# Verna_Dorian_334CC.net
KiCad netlist of a schematic drawn in EAGLE
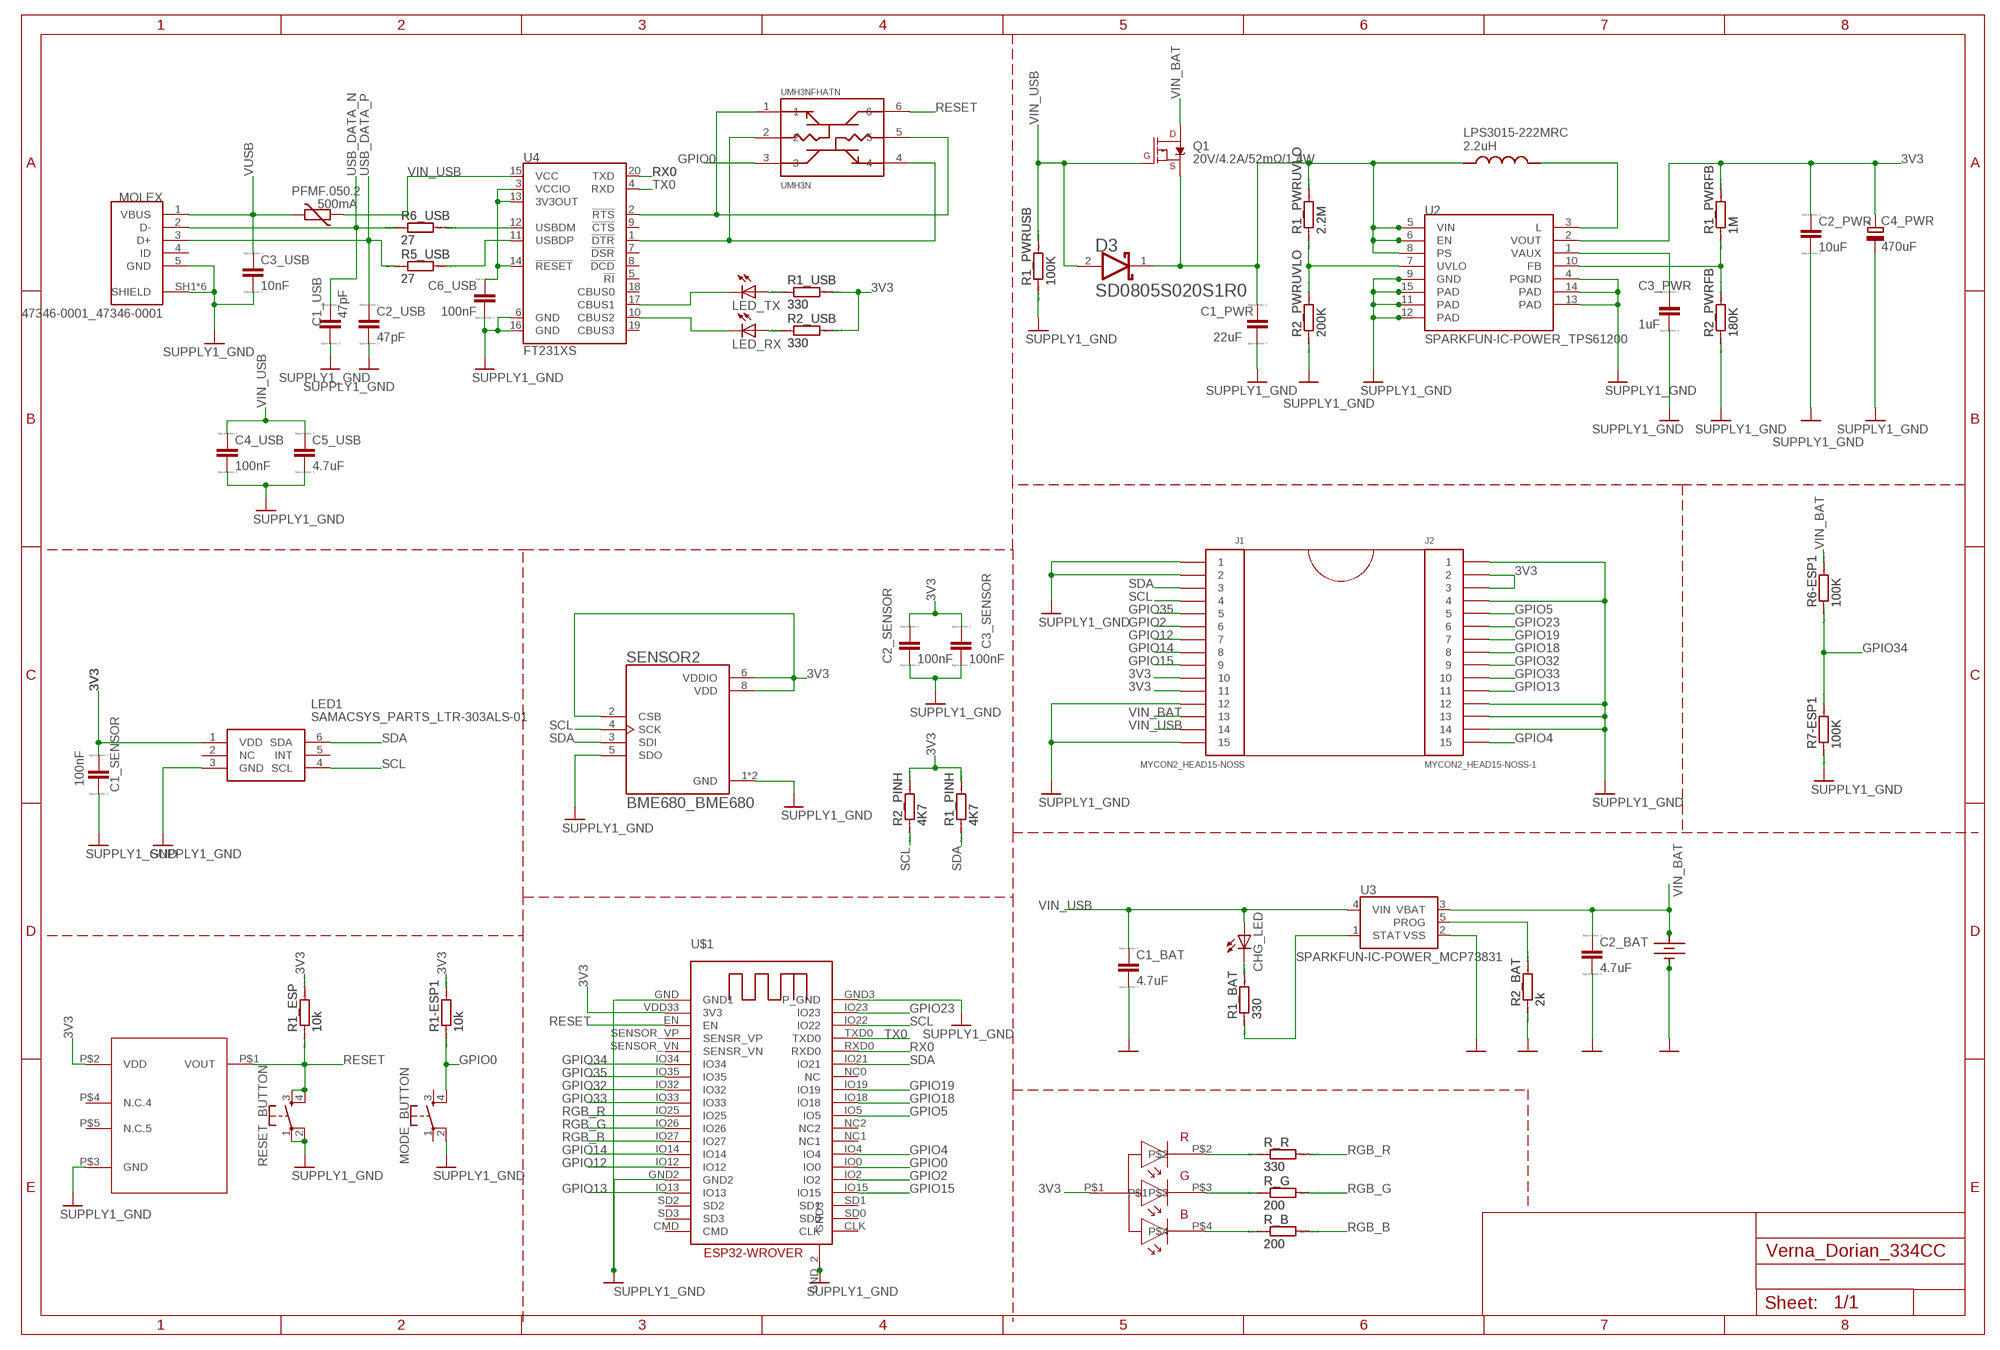
[diagram p0: schematic, sheet 1]

(export (version "E")
  (design (tool "Eeschema 10.0.6"))
  (components
    (comp (ref "18650BATTHOLDER")
      (value "12BHC186CLP-GR_12BHC186CLP-GR")
      (footprint "eagle-import:12BHC186CLP-GR_12BHC186CLP-GR")
      (libsource (lib "eagle-import") (part "12BHC186CLP-GR_12BHC186CLP-GR"))
    )
    (comp (ref "C1_BAT")
      (value "4.7uF")
      (footprint "eagle-import:EAGLE-LTSPICE_C0402")
      (libsource (lib "eagle-import") (part "EAGLE-LTSPICE_CC0402"))
    )
    (comp (ref "C1_PWR")
      (value "22uF")
      (footprint "eagle-import:EAGLE-LTSPICE_C0402")
      (libsource (lib "eagle-import") (part "EAGLE-LTSPICE_CC0402"))
    )
    (comp (ref "C1_SENSOR")
      (value "100nF")
      (footprint "eagle-import:EAGLE-LTSPICE_C0402")
      (libsource (lib "eagle-import") (part "EAGLE-LTSPICE_CC0402"))
    )
    (comp (ref "C1_USB")
      (value "47pF")
      (footprint "eagle-import:EAGLE-LTSPICE_C0402")
      (libsource (lib "eagle-import") (part "EAGLE-LTSPICE_CC0402"))
    )
    (comp (ref "C2_BAT")
      (value "4.7uF")
      (footprint "eagle-import:EAGLE-LTSPICE_C0402")
      (libsource (lib "eagle-import") (part "EAGLE-LTSPICE_CC0402"))
    )
    (comp (ref "C2_PWR")
      (value "10uF")
      (footprint "eagle-import:EAGLE-LTSPICE_C0402")
      (libsource (lib "eagle-import") (part "EAGLE-LTSPICE_CC0402"))
    )
    (comp (ref "C2_SENSOR")
      (value "100nF")
      (footprint "eagle-import:EAGLE-LTSPICE_C0402")
      (libsource (lib "eagle-import") (part "EAGLE-LTSPICE_CC0402"))
    )
    (comp (ref "C2_USB")
      (value "47pF")
      (footprint "eagle-import:EAGLE-LTSPICE_C0402")
      (libsource (lib "eagle-import") (part "EAGLE-LTSPICE_CC0402"))
    )
    (comp (ref "C3_PWR")
      (value "1uF")
      (footprint "eagle-import:EAGLE-LTSPICE_C0402")
      (libsource (lib "eagle-import") (part "EAGLE-LTSPICE_CC0402"))
    )
    (comp (ref "C3_SENSOR")
      (value "100nF")
      (footprint "eagle-import:EAGLE-LTSPICE_C0402")
      (libsource (lib "eagle-import") (part "EAGLE-LTSPICE_CC0402"))
    )
    (comp (ref "C3_USB")
      (value "10nF")
      (footprint "eagle-import:EAGLE-LTSPICE_C0402")
      (libsource (lib "eagle-import") (part "EAGLE-LTSPICE_CC0402"))
    )
    (comp (ref "C4_PWR")
      (value "470uF")
      (footprint "eagle-import:RCL_D_7343-31R")
      (libsource (lib "eagle-import") (part "RCL_CPOL-EUD/7343-31R"))
    )
    (comp (ref "C4_USB")
      (value "100nF")
      (footprint "eagle-import:EAGLE-LTSPICE_C0402")
      (libsource (lib "eagle-import") (part "EAGLE-LTSPICE_CC0402"))
    )
    (comp (ref "C5_USB")
      (value "4.7uF")
      (footprint "eagle-import:EAGLE-LTSPICE_C0402")
      (libsource (lib "eagle-import") (part "EAGLE-LTSPICE_CC0402"))
    )
    (comp (ref "C6_USB")
      (value "100nF")
      (footprint "eagle-import:EAGLE-LTSPICE_C0402")
      (libsource (lib "eagle-import") (part "EAGLE-LTSPICE_CC0402"))
    )
    (comp (ref "CHG_LED")
      (value "ADAFRUIT_LEDCHIP-LED0603")
      (footprint "eagle-import:ADAFRUIT_CHIP-LED0603")
      (libsource (lib "eagle-import") (part "ADAFRUIT_LEDCHIP-LED0603"))
    )
    (comp (ref "D3")
      (value "AVX---SD0805S020S1R0_AVX_SD0805S020S1R0AVX_SD0805S020S1R0_0_0")
      (footprint "eagle-import:AVX---SD0805S020S1R0_AVX_SD0805S020S1R0_0")
      (fields
        (field (name "DIGIKEY_PART_NUMBER") "478-7800-1-ND")
        (field (name "MF") "AVX")
        (field (name "MOUSER_PART_NUMBER") "581-SD0805S020S1R0")
      )
      (libsource (lib "eagle-import") (part "AVX---SD0805S020S1R0_AVX_SD0805S020S1R0AVX_SD0805S020S1R0_0_0"))
    )
    (comp (ref "J1")
      (value "MYCON2_HEAD15-NOSS")
      (footprint "eagle-import:MYCON2_HEAD15-NOSS")
      (libsource (lib "eagle-import") (part "MYCON2_HEAD15-NOSS"))
    )
    (comp (ref "J2")
      (value "MYCON2_HEAD15-NOSS-1")
      (footprint "eagle-import:MYCON2_HEAD15-NOSS-1")
      (libsource (lib "eagle-import") (part "MYCON2_HEAD15-NOSS-1"))
    )
    (comp (ref "LED1")
      (value "SAMACSYS_PARTS_LTR-303ALS-01")
      (footprint "eagle-import:SAMACSYS_PARTS_LTR303ALS01")
      (fields
        (field (name "ARROW_PART_NUMBER") "LTR-303ALS-01")
        (field (name "MOUSER_PART_NUMBER") "859-LTR-303ALS-01")
      )
      (libsource (lib "eagle-import") (part "SAMACSYS_PARTS_LTR-303ALS-01"))
    )
    (comp (ref "LED_RX")
      (value "ADAFRUIT_LEDCHIP-LED0603")
      (footprint "eagle-import:ADAFRUIT_CHIP-LED0603")
      (libsource (lib "eagle-import") (part "ADAFRUIT_LEDCHIP-LED0603"))
    )
    (comp (ref "LED_TX")
      (value "ADAFRUIT_LEDCHIP-LED0603")
      (footprint "eagle-import:ADAFRUIT_CHIP-LED0603")
      (libsource (lib "eagle-import") (part "ADAFRUIT_LEDCHIP-LED0603"))
    )
    (comp (ref "MODE_BUTTON")
      (value "SPARKFUN-SWITCHES_MOMENTARY-SWITCH-SPST-2-SMD-4.6X2.8MM")
      (footprint "eagle-import:SPARKFUN-SWITCHES_TACTILE_SWITCH_SMD_4.6X2.8MM")
      (libsource (lib "eagle-import") (part "SPARKFUN-SWITCHES_MOMENTARY-SWITCH-SPST-2-SMD-4.6X2.8MM"))
    )
    (comp (ref "MOLEX")
      (value "47346-0001_47346-0001")
      (footprint "eagle-import:47346-0001_MOLEX_47346-0001")
      (fields (field (name "MF") "Molex") (field (name "MP") "47346-0001"))
      (libsource (lib "eagle-import") (part "47346-0001_47346-0001"))
    )
    (comp (ref "PFMF.050.2")
      (value "500mA")
      (footprint "eagle-import:VARISTOR_CT_CN1812")
      (libsource (lib "eagle-import") (part "VARISTOR_VARISTORCN1812"))
    )
    (comp (ref "Q1")
      (value "20V/4.2A/52mΩ/1.4W")
      (footprint "eagle-import:SPARKFUN-DISCRETESEMI_SOT23-3")
      (libsource (lib "eagle-import") (part "SPARKFUN-DISCRETESEMI_MOSFET_PCH-DMG2305UX-7"))
    )
    (comp (ref "R1-ESP1")
      (value "10k")
      (footprint "eagle-import:EAGLE-LTSPICE_R0402")
      (libsource (lib "eagle-import") (part "EAGLE-LTSPICE_RR0402"))
    )
    (comp (ref "R1_BAT")
      (value "330")
      (footprint "eagle-import:EAGLE-LTSPICE_R0402")
      (libsource (lib "eagle-import") (part "EAGLE-LTSPICE_RR0402"))
    )
    (comp (ref "R1_ESP")
      (value "10k")
      (footprint "eagle-import:EAGLE-LTSPICE_R0402")
      (libsource (lib "eagle-import") (part "EAGLE-LTSPICE_RR0402"))
    )
    (comp (ref "R1_PINH")
      (value "4K7")
      (footprint "eagle-import:EAGLE-LTSPICE_R0402")
      (libsource (lib "eagle-import") (part "EAGLE-LTSPICE_RR0402"))
    )
    (comp (ref "R1_PWRFB")
      (value "1M")
      (footprint "eagle-import:EAGLE-LTSPICE_R0402")
      (libsource (lib "eagle-import") (part "EAGLE-LTSPICE_RR0402"))
    )
    (comp (ref "R1_PWRUSB")
      (value "100K")
      (footprint "eagle-import:EAGLE-LTSPICE_R0402")
      (libsource (lib "eagle-import") (part "EAGLE-LTSPICE_RR0402"))
    )
    (comp (ref "R1_PWRUVLO")
      (value "2.2M")
      (footprint "eagle-import:EAGLE-LTSPICE_R0402")
      (libsource (lib "eagle-import") (part "EAGLE-LTSPICE_RR0402"))
    )
    (comp (ref "R1_USB")
      (value "330")
      (footprint "eagle-import:EAGLE-LTSPICE_R0402")
      (libsource (lib "eagle-import") (part "EAGLE-LTSPICE_RR0402"))
    )
    (comp (ref "R2_BAT")
      (value "2k")
      (footprint "eagle-import:EAGLE-LTSPICE_R0402")
      (libsource (lib "eagle-import") (part "EAGLE-LTSPICE_RR0402"))
    )
    (comp (ref "R2_PINH")
      (value "4K7")
      (footprint "eagle-import:EAGLE-LTSPICE_R0402")
      (libsource (lib "eagle-import") (part "EAGLE-LTSPICE_RR0402"))
    )
    (comp (ref "R2_PWRFB")
      (value "180K")
      (footprint "eagle-import:EAGLE-LTSPICE_R0402")
      (libsource (lib "eagle-import") (part "EAGLE-LTSPICE_RR0402"))
    )
    (comp (ref "R2_PWRUVLO")
      (value "200K")
      (footprint "eagle-import:EAGLE-LTSPICE_R0402")
      (libsource (lib "eagle-import") (part "EAGLE-LTSPICE_RR0402"))
    )
    (comp (ref "R2_USB")
      (value "330")
      (footprint "eagle-import:EAGLE-LTSPICE_R0402")
      (libsource (lib "eagle-import") (part "EAGLE-LTSPICE_RR0402"))
    )
    (comp (ref "R5_USB")
      (value "27")
      (footprint "eagle-import:EAGLE-LTSPICE_R0402")
      (libsource (lib "eagle-import") (part "EAGLE-LTSPICE_RR0402"))
    )
    (comp (ref "R6-ESP1")
      (value "100K")
      (footprint "eagle-import:EAGLE-LTSPICE_R0402")
      (libsource (lib "eagle-import") (part "EAGLE-LTSPICE_RR0402"))
    )
    (comp (ref "R6_USB")
      (value "27")
      (footprint "eagle-import:EAGLE-LTSPICE_R0402")
      (libsource (lib "eagle-import") (part "EAGLE-LTSPICE_RR0402"))
    )
    (comp (ref "R7-ESP1")
      (value "100K")
      (footprint "eagle-import:EAGLE-LTSPICE_R0402")
      (libsource (lib "eagle-import") (part "EAGLE-LTSPICE_RR0402"))
    )
    (comp (ref "RESET_BUTTON")
      (value "SPARKFUN-SWITCHES_MOMENTARY-SWITCH-SPST-2-SMD-4.6X2.8MM")
      (footprint "eagle-import:SPARKFUN-SWITCHES_TACTILE_SWITCH_SMD_4.6X2.8MM")
      (libsource (lib "eagle-import") (part "SPARKFUN-SWITCHES_MOMENTARY-SWITCH-SPST-2-SMD-4.6X2.8MM"))
    )
    (comp (ref "R_B")
      (value "200")
      (footprint "eagle-import:EAGLE-LTSPICE_R0402")
      (libsource (lib "eagle-import") (part "EAGLE-LTSPICE_RR0402"))
    )
    (comp (ref "R_G")
      (value "200")
      (footprint "eagle-import:EAGLE-LTSPICE_R0402")
      (libsource (lib "eagle-import") (part "EAGLE-LTSPICE_RR0402"))
    )
    (comp (ref "R_R")
      (value "330")
      (footprint "eagle-import:EAGLE-LTSPICE_R0402")
      (libsource (lib "eagle-import") (part "EAGLE-LTSPICE_RR0402"))
    )
    (comp (ref "SENSOR2")
      (value "BME680_BME680")
      (footprint "eagle-import:BME680_PSON80P300X300X100-8N")
      (fields (field (name "MF") "Bosch Sensortec") (field (name "MP") "BME680"))
      (libsource (lib "eagle-import") (part "BME680_BME680"))
    )
    (comp (ref "U$1")
      (value "ESP32-WROVER_ESP32-WROVER")
      (footprint "eagle-import:ESP32-WROVER_ESP32-WROVER")
      (libsource (lib "eagle-import") (part "ESP32-WROVER_ESP32-WROVER"))
    )
    (comp (ref "U$2")
      (value "150202M153130_150202M153130-RGB")
      (footprint "eagle-import:150202M153130_150202M153130")
      (libsource (lib "eagle-import") (part "150202M153130_150202M153130-RGB"))
    )
    (comp (ref "U$3")
      (value "BD48E27G-TR_BD48E27G-TR")
      (footprint "eagle-import:BD48E27G-TR_SSOP5")
      (libsource (lib "eagle-import") (part "BD48E27G-TR_BD48E27G-TR"))
    )
    (comp (ref "U$6")
      (value "LPS3015_LPS3015")
      (footprint "eagle-import:LPS3015_LPS3015-222MRC")
      (libsource (lib "eagle-import") (part "LPS3015_LPS3015"))
    )
    (comp (ref "U2")
      (value "SPARKFUN-IC-POWER_TPS61200")
      (footprint "eagle-import:SPARKFUN-IC-POWER_QFN-10_PAD")
      (libsource (lib "eagle-import") (part "SPARKFUN-IC-POWER_TPS61200"))
    )
    (comp (ref "U3")
      (value "SPARKFUN-IC-POWER_MCP73831")
      (footprint "eagle-import:SPARKFUN-IC-POWER_SOT23-5")
      (libsource (lib "eagle-import") (part "SPARKFUN-IC-POWER_MCP73831"))
    )
    (comp (ref "U4")
      (value "FT231XS")
      (footprint "eagle-import:SPARKFUN-IC-COMMS_SSOP20_L")
      (libsource (lib "eagle-import") (part "SPARKFUN-IC-COMMS_FT231XS"))
    )
    (comp (ref "UMH3NFHATN")
      (value "UMH3N_UMH3N")
      (footprint "eagle-import:UMH3N_SOP65P210X100-6N")
      (fields (field (name "MF") "Rohm") (field (name "MP") "UMH3N"))
      (libsource (lib "eagle-import") (part "UMH3N_UMH3N"))
    )
  )
  (nets
    (net (code "1") (name "/3V3") (class "Default")
      (node (ref "C1_SENSOR") (pin "1") (pinfunction "1_1") (pintype "passive"))
      (node (ref "C2_PWR") (pin "1") (pinfunction "1_1") (pintype "passive"))
      (node (ref "C2_SENSOR") (pin "1") (pinfunction "1_1") (pintype "passive"))
      (node (ref "C3_SENSOR") (pin "1") (pinfunction "1_1") (pintype "passive"))
      (node (ref "C4_PWR") (pin "+") (pinfunction "+_+") (pintype "passive"))
      (node (ref "J1") (pin "10") (pinfunction "10_10") (pintype "passive"))
      (node (ref "J1") (pin "11") (pinfunction "11_11") (pintype "passive"))
      (node (ref "J2") (pin "2") (pinfunction "2_2") (pintype "passive"))
      (node (ref "J2") (pin "3") (pinfunction "3_3") (pintype "passive"))
      (node (ref "LED1") (pin "1") (pinfunction "VDD_1") (pintype "bidirectional"))
      (node (ref "R1-ESP1") (pin "2") (pinfunction "2_2") (pintype "passive"))
      (node (ref "R1_ESP") (pin "2") (pinfunction "2_2") (pintype "passive"))
      (node (ref "R1_PINH") (pin "2") (pinfunction "2_2") (pintype "passive"))
      (node (ref "R1_PWRFB") (pin "2") (pinfunction "2_2") (pintype "passive"))
      (node (ref "R1_USB") (pin "2") (pinfunction "2_2") (pintype "passive"))
      (node (ref "R2_PINH") (pin "2") (pinfunction "2_2") (pintype "passive"))
      (node (ref "R2_USB") (pin "2") (pinfunction "2_2") (pintype "passive"))
      (node (ref "SENSOR2") (pin "2") (pinfunction "CSB_2") (pintype "input"))
      (node (ref "SENSOR2") (pin "6") (pinfunction "VDDIO_6") (pintype "power_in"))
      (node (ref "SENSOR2") (pin "8") (pinfunction "VDD_8") (pintype "power_in"))
      (node (ref "U$1") (pin "VDD33") (pinfunction "3V3_VDD33") (pintype "bidirectional"))
      (node (ref "U$2") (pin "P$1") (pinfunction "P$1_P$1") (pintype "bidirectional"))
      (node (ref "U$3") (pin "P$2") (pinfunction "VDD_P$2") (pintype "bidirectional"))
      (node (ref "U2") (pin "2") (pinfunction "VOUT_2") (pintype "passive"))
    )
    (net (code "2") (name "/GPIO0") (class "Default")
      (node (ref "MODE_BUTTON") (pin "4") (pinfunction "4_4") (pintype "passive"))
      (node (ref "R1-ESP1") (pin "1") (pinfunction "1_1") (pintype "passive"))
      (node (ref "U$1") (pin "IO0") (pinfunction "IO0_IO0") (pintype "bidirectional"))
      (node (ref "UMH3NFHATN") (pin "3") (pinfunction "3_3") (pintype "bidirectional"))
    )
    (net (code "3") (name "/GPIO2") (class "Default")
      (node (ref "J1") (pin "6") (pinfunction "6_6") (pintype "passive"))
      (node (ref "U$1") (pin "IO2") (pinfunction "IO2_IO2") (pintype "bidirectional"))
    )
    (net (code "4") (name "/GPIO4") (class "Default")
      (node (ref "J2") (pin "15") (pinfunction "15_15") (pintype "passive"))
      (node (ref "U$1") (pin "IO4") (pinfunction "IO4_IO4") (pintype "bidirectional"))
    )
    (net (code "5") (name "/GPIO5") (class "Default")
      (node (ref "J2") (pin "5") (pinfunction "5_5") (pintype "passive"))
      (node (ref "U$1") (pin "IO5") (pinfunction "IO5_IO5") (pintype "bidirectional"))
    )
    (net (code "6") (name "/GPIO12") (class "Default")
      (node (ref "J1") (pin "7") (pinfunction "7_7") (pintype "passive"))
      (node (ref "U$1") (pin "IO12") (pinfunction "IO12_IO12") (pintype "bidirectional"))
    )
    (net (code "7") (name "/GPIO13") (class "Default")
      (node (ref "J2") (pin "11") (pinfunction "11_11") (pintype "passive"))
      (node (ref "U$1") (pin "IO13") (pinfunction "IO13_IO13") (pintype "bidirectional"))
    )
    (net (code "8") (name "/GPIO14") (class "Default")
      (node (ref "J1") (pin "8") (pinfunction "8_8") (pintype "passive"))
      (node (ref "U$1") (pin "IO14") (pinfunction "IO14_IO14") (pintype "bidirectional"))
    )
    (net (code "9") (name "/GPIO15") (class "Default")
      (node (ref "J1") (pin "9") (pinfunction "9_9") (pintype "passive"))
      (node (ref "U$1") (pin "IO15") (pinfunction "IO15_IO15") (pintype "bidirectional"))
    )
    (net (code "10") (name "/GPIO18") (class "Default")
      (node (ref "J2") (pin "8") (pinfunction "8_8") (pintype "passive"))
      (node (ref "U$1") (pin "IO18") (pinfunction "IO18_IO18") (pintype "bidirectional"))
    )
    (net (code "11") (name "/GPIO19") (class "Default")
      (node (ref "J2") (pin "7") (pinfunction "7_7") (pintype "passive"))
      (node (ref "U$1") (pin "IO19") (pinfunction "IO19_IO19") (pintype "bidirectional"))
    )
    (net (code "12") (name "/GPIO23") (class "Default")
      (node (ref "J2") (pin "6") (pinfunction "6_6") (pintype "passive"))
      (node (ref "U$1") (pin "IO23") (pinfunction "IO23_IO23") (pintype "bidirectional"))
    )
    (net (code "13") (name "/GPIO32") (class "Default")
      (node (ref "J2") (pin "9") (pinfunction "9_9") (pintype "passive"))
      (node (ref "U$1") (pin "IO32") (pinfunction "IO32_IO32") (pintype "bidirectional"))
    )
    (net (code "14") (name "/GPIO33") (class "Default")
      (node (ref "J2") (pin "10") (pinfunction "10_10") (pintype "passive"))
      (node (ref "U$1") (pin "IO33") (pinfunction "IO33_IO33") (pintype "bidirectional"))
    )
    (net (code "15") (name "/GPIO34") (class "Default")
      (node (ref "R6-ESP1") (pin "1") (pinfunction "1_1") (pintype "passive"))
      (node (ref "R7-ESP1") (pin "2") (pinfunction "2_2") (pintype "passive"))
      (node (ref "U$1") (pin "IO34") (pinfunction "IO34_IO34") (pintype "bidirectional"))
    )
    (net (code "16") (name "/GPIO35") (class "Default")
      (node (ref "J1") (pin "5") (pinfunction "5_5") (pintype "passive"))
      (node (ref "U$1") (pin "IO35") (pinfunction "IO35_IO35") (pintype "bidirectional"))
    )
    (net (code "17") (name "/RESET") (class "Default")
      (node (ref "R1_ESP") (pin "1") (pinfunction "1_1") (pintype "passive"))
      (node (ref "RESET_BUTTON") (pin "3") (pinfunction "3_3") (pintype "passive"))
      (node (ref "RESET_BUTTON") (pin "4") (pinfunction "4_4") (pintype "passive"))
      (node (ref "U$1") (pin "EN") (pinfunction "EN_EN") (pintype "bidirectional"))
      (node (ref "U$3") (pin "P$1") (pinfunction "VOUT_P$1") (pintype "bidirectional"))
      (node (ref "UMH3NFHATN") (pin "6") (pinfunction "6_6") (pintype "bidirectional"))
    )
    (net (code "18") (name "/RGB_B") (class "Default")
      (node (ref "R_B") (pin "2") (pinfunction "2_2") (pintype "passive"))
      (node (ref "U$1") (pin "IO27") (pinfunction "IO27_IO27") (pintype "bidirectional"))
    )
    (net (code "19") (name "/RGB_G") (class "Default")
      (node (ref "R_G") (pin "2") (pinfunction "2_2") (pintype "passive"))
      (node (ref "U$1") (pin "IO26") (pinfunction "IO26_IO26") (pintype "bidirectional"))
    )
    (net (code "20") (name "/RGB_R") (class "Default")
      (node (ref "R_R") (pin "2") (pinfunction "2_2") (pintype "passive"))
      (node (ref "U$1") (pin "IO25") (pinfunction "IO25_IO25") (pintype "bidirectional"))
    )
    (net (code "21") (name "/RX0") (class "Default")
      (node (ref "U$1") (pin "RXD0") (pinfunction "RXD0_RXD0") (pintype "bidirectional"))
      (node (ref "U4") (pin "20") (pinfunction "TXD_20") (pintype "bidirectional"))
    )
    (net (code "22") (name "/SCL") (class "Default")
      (node (ref "J1") (pin "4") (pinfunction "4_4") (pintype "passive"))
      (node (ref "LED1") (pin "4") (pinfunction "SCL_4") (pintype "bidirectional"))
      (node (ref "R2_PINH") (pin "1") (pinfunction "1_1") (pintype "passive"))
      (node (ref "SENSOR2") (pin "4") (pinfunction "SCK_4") (pintype "input"))
      (node (ref "U$1") (pin "IO22") (pinfunction "IO22_IO22") (pintype "bidirectional"))
    )
    (net (code "23") (name "/SDA") (class "Default")
      (node (ref "J1") (pin "3") (pinfunction "3_3") (pintype "passive"))
      (node (ref "LED1") (pin "6") (pinfunction "SDA_6") (pintype "bidirectional"))
      (node (ref "R1_PINH") (pin "1") (pinfunction "1_1") (pintype "passive"))
      (node (ref "SENSOR2") (pin "3") (pinfunction "SDI_3") (pintype "bidirectional"))
      (node (ref "U$1") (pin "IO21") (pinfunction "IO21_IO21") (pintype "bidirectional"))
    )
    (net (code "24") (name "/TX0") (class "Default")
      (node (ref "U$1") (pin "TXD0") (pinfunction "TXD0_TXD0") (pintype "bidirectional"))
      (node (ref "U4") (pin "4") (pinfunction "RXD_4") (pintype "bidirectional"))
    )
    (net (code "25") (name "/USB_DATA_N") (class "Default")
      (node (ref "C1_USB") (pin "1") (pinfunction "1_1") (pintype "passive"))
      (node (ref "MOLEX") (pin "2") (pinfunction "D-_2") (pintype "bidirectional"))
      (node (ref "R6_USB") (pin "1") (pinfunction "1_1") (pintype "passive"))
    )
    (net (code "26") (name "/USB_DATA_P") (class "Default")
      (node (ref "C2_USB") (pin "1") (pinfunction "1_1") (pintype "passive"))
      (node (ref "MOLEX") (pin "3") (pinfunction "D+_3") (pintype "bidirectional"))
      (node (ref "R5_USB") (pin "1") (pinfunction "1_1") (pintype "passive"))
    )
    (net (code "27") (name "/VIN_BAT") (class "Default")
      (node (ref "18650BATTHOLDER") (pin "P$2") (pinfunction "P_P$2") (pintype "bidirectional"))
      (node (ref "18650BATTHOLDER") (pin "P$5") (pinfunction "P_P$5") (pintype "bidirectional"))
      (node (ref "18650BATTHOLDER") (pin "P$6") (pinfunction "P_P$6") (pintype "bidirectional"))
      (node (ref "C2_BAT") (pin "1") (pinfunction "1_1") (pintype "passive"))
      (node (ref "J1") (pin "13") (pinfunction "13_13") (pintype "passive"))
      (node (ref "Q1") (pin "3") (pinfunction "D_3") (pintype "bidirectional"))
      (node (ref "R6-ESP1") (pin "2") (pinfunction "2_2") (pintype "passive"))
      (node (ref "U3") (pin "3") (pinfunction "VBAT_3") (pintype "power_in"))
    )
    (net (code "28") (name "/VIN_USB") (class "Default")
      (node (ref "C1_BAT") (pin "1") (pinfunction "1_1") (pintype "passive"))
      (node (ref "C4_USB") (pin "1") (pinfunction "1_1") (pintype "passive"))
      (node (ref "C5_USB") (pin "1") (pinfunction "1_1") (pintype "passive"))
      (node (ref "CHG_LED") (pin "A") (pinfunction "A_A") (pintype "passive"))
      (node (ref "D3") (pin "2") (pinfunction "ANODE_2") (pintype "bidirectional"))
      (node (ref "J1") (pin "14") (pinfunction "14_14") (pintype "passive"))
      (node (ref "PFMF.050.2") (pin "1") (pinfunction "1_1") (pintype "passive"))
      (node (ref "Q1") (pin "1") (pinfunction "G_1") (pintype "bidirectional"))
      (node (ref "R1_PWRUSB") (pin "2") (pinfunction "2_2") (pintype "passive"))
      (node (ref "U3") (pin "4") (pinfunction "VIN_4") (pintype "power_in"))
      (node (ref "U4") (pin "15") (pinfunction "VCC_15") (pintype "bidirectional"))
    )
    (net (code "29") (name "/VUSB") (class "Default")
      (node (ref "C3_USB") (pin "1") (pinfunction "1_1") (pintype "passive"))
      (node (ref "MOLEX") (pin "1") (pinfunction "VBUS_1") (pintype "power_in"))
      (node (ref "PFMF.050.2") (pin "2") (pinfunction "2_2") (pintype "passive"))
    )
    (net (code "30") (name "Net-(CHG_LED-PadC)") (class "Default")
      (node (ref "CHG_LED") (pin "C") (pinfunction "C_C") (pintype "passive"))
      (node (ref "R1_BAT") (pin "2") (pinfunction "2_2") (pintype "passive"))
    )
    (net (code "31") (name "Net-(D3-CATHODE)") (class "Default")
      (node (ref "C1_PWR") (pin "1") (pinfunction "1_1") (pintype "passive"))
      (node (ref "D3") (pin "1") (pinfunction "CATHODE_1") (pintype "bidirectional"))
      (node (ref "Q1") (pin "2") (pinfunction "S_2") (pintype "bidirectional"))
      (node (ref "R1_PWRUVLO") (pin "2") (pinfunction "2_2") (pintype "passive"))
      (node (ref "U$6") (pin "P$1") (pinfunction "P$1_P$1") (pintype "bidirectional"))
      (node (ref "U2") (pin "5") (pinfunction "VIN_5") (pintype "power_in"))
      (node (ref "U2") (pin "6") (pinfunction "EN_6") (pintype "input"))
      (node (ref "U2") (pin "8") (pinfunction "PS_8") (pintype "input"))
    )
    (net (code "32") (name "Net-(LED_RX-PadA)") (class "Default")
      (node (ref "LED_RX") (pin "A") (pinfunction "A_A") (pintype "passive"))
      (node (ref "R2_USB") (pin "1") (pinfunction "1_1") (pintype "passive"))
    )
    (net (code "33") (name "Net-(LED_TX-PadA)") (class "Default")
      (node (ref "LED_TX") (pin "A") (pinfunction "A_A") (pintype "passive"))
      (node (ref "R1_USB") (pin "1") (pinfunction "1_1") (pintype "passive"))
    )
    (net (code "34") (name "Net-(R_B-Pad1)") (class "Default")
      (node (ref "R_B") (pin "1") (pinfunction "1_1") (pintype "passive"))
      (node (ref "U$2") (pin "P$4") (pinfunction "P$4_P$4") (pintype "bidirectional"))
    )
    (net (code "35") (name "Net-(R_G-Pad1)") (class "Default")
      (node (ref "R_G") (pin "1") (pinfunction "1_1") (pintype "passive"))
      (node (ref "U$2") (pin "P$3") (pinfunction "P$3_P$3") (pintype "bidirectional"))
    )
    (net (code "36") (name "Net-(R_R-Pad1)") (class "Default")
      (node (ref "R_R") (pin "1") (pinfunction "1_1") (pintype "passive"))
      (node (ref "U$2") (pin "P$2") (pinfunction "P$2_P$2") (pintype "bidirectional"))
    )
    (net (code "37") (name "Net-(U2-FB)") (class "Default")
      (node (ref "R1_PWRFB") (pin "1") (pinfunction "1_1") (pintype "passive"))
      (node (ref "R2_PWRFB") (pin "2") (pinfunction "2_2") (pintype "passive"))
      (node (ref "U2") (pin "10") (pinfunction "FB_10") (pintype "passive"))
    )
    (net (code "38") (name "Net-(U2-L)") (class "Default")
      (node (ref "U$6") (pin "P$2") (pinfunction "P$2_P$2") (pintype "bidirectional"))
      (node (ref "U2") (pin "3") (pinfunction "L_3") (pintype "passive"))
    )
    (net (code "39") (name "Net-(U2-UVLO)") (class "Default")
      (node (ref "R1_PWRUVLO") (pin "1") (pinfunction "1_1") (pintype "passive"))
      (node (ref "R2_PWRUVLO") (pin "2") (pinfunction "2_2") (pintype "passive"))
      (node (ref "U2") (pin "7") (pinfunction "UVLO_7") (pintype "passive"))
    )
    (net (code "40") (name "Net-(U2-VAUX)") (class "Default")
      (node (ref "C3_PWR") (pin "1") (pinfunction "1_1") (pintype "passive"))
      (node (ref "U2") (pin "1") (pinfunction "VAUX_1") (pintype "passive"))
    )
    (net (code "41") (name "Net-(U3-PROG)") (class "Default")
      (node (ref "R2_BAT") (pin "2") (pinfunction "2_2") (pintype "passive"))
      (node (ref "U3") (pin "5") (pinfunction "PROG_5") (pintype "input"))
    )
    (net (code "42") (name "Net-(U3-STAT)") (class "Default")
      (node (ref "R1_BAT") (pin "1") (pinfunction "1_1") (pintype "passive"))
      (node (ref "U3") (pin "1") (pinfunction "STAT_1") (pintype "output"))
    )
    (net (code "43") (name "Net-(U4-3V3OUT)") (class "Default")
      (node (ref "C6_USB") (pin "1") (pinfunction "1_1") (pintype "passive"))
      (node (ref "U4") (pin "13") (pinfunction "3V3OUT_13") (pintype "bidirectional"))
      (node (ref "U4") (pin "14") (pinfunction "~{RESET}_14") (pintype "bidirectional"))
      (node (ref "U4") (pin "3") (pinfunction "VCCIO_3") (pintype "bidirectional"))
    )
    (net (code "44") (name "Net-(U4-CBUS1)") (class "Default")
      (node (ref "LED_TX") (pin "C") (pinfunction "C_C") (pintype "passive"))
      (node (ref "U4") (pin "17") (pinfunction "CBUS1_17") (pintype "bidirectional"))
    )
    (net (code "45") (name "Net-(U4-CBUS2)") (class "Default")
      (node (ref "LED_RX") (pin "C") (pinfunction "C_C") (pintype "passive"))
      (node (ref "U4") (pin "10") (pinfunction "CBUS2_10") (pintype "bidirectional"))
    )
    (net (code "46") (name "Net-(U4-USBDM)") (class "Default")
      (node (ref "R6_USB") (pin "2") (pinfunction "2_2") (pintype "passive"))
      (node (ref "U4") (pin "12") (pinfunction "USBDM_12") (pintype "bidirectional"))
    )
    (net (code "47") (name "Net-(U4-USBDP)") (class "Default")
      (node (ref "R5_USB") (pin "2") (pinfunction "2_2") (pintype "passive"))
      (node (ref "U4") (pin "11") (pinfunction "USBDP_11") (pintype "bidirectional"))
    )
    (net (code "48") (name "Net-(U4-~{DTR})") (class "Default")
      (node (ref "U4") (pin "1") (pinfunction "~{DTR}_1") (pintype "bidirectional"))
      (node (ref "UMH3NFHATN") (pin "2") (pinfunction "2_2") (pintype "bidirectional"))
      (node (ref "UMH3NFHATN") (pin "4") (pinfunction "4_4") (pintype "bidirectional"))
    )
    (net (code "49") (name "Net-(U4-~{RTS})") (class "Default")
      (node (ref "U4") (pin "2") (pinfunction "~{RTS}_2") (pintype "bidirectional"))
      (node (ref "UMH3NFHATN") (pin "1") (pinfunction "1_1") (pintype "bidirectional"))
      (node (ref "UMH3NFHATN") (pin "5") (pinfunction "5_5") (pintype "bidirectional"))
    )
    (net (code "50") (name "SUPPLY1_GND") (class "Default")
      (node (ref "18650BATTHOLDER") (pin "P$1") (pinfunction "G_P$1") (pintype "bidirectional"))
      (node (ref "18650BATTHOLDER") (pin "P$3") (pinfunction "G_P$3") (pintype "bidirectional"))
      (node (ref "18650BATTHOLDER") (pin "P$4") (pinfunction "G_P$4") (pintype "bidirectional"))
      (node (ref "C1_BAT") (pin "2") (pinfunction "2_2") (pintype "passive"))
      (node (ref "C1_PWR") (pin "2") (pinfunction "2_2") (pintype "passive"))
      (node (ref "C1_SENSOR") (pin "2") (pinfunction "2_2") (pintype "passive"))
      (node (ref "C1_USB") (pin "2") (pinfunction "2_2") (pintype "passive"))
      (node (ref "C2_BAT") (pin "2") (pinfunction "2_2") (pintype "passive"))
      (node (ref "C2_PWR") (pin "2") (pinfunction "2_2") (pintype "passive"))
      (node (ref "C2_SENSOR") (pin "2") (pinfunction "2_2") (pintype "passive"))
      (node (ref "C2_USB") (pin "2") (pinfunction "2_2") (pintype "passive"))
      (node (ref "C3_PWR") (pin "2") (pinfunction "2_2") (pintype "passive"))
      (node (ref "C3_SENSOR") (pin "2") (pinfunction "2_2") (pintype "passive"))
      (node (ref "C3_USB") (pin "2") (pinfunction "2_2") (pintype "passive"))
      (node (ref "C4_PWR") (pin "-") (pinfunction "-_-") (pintype "passive"))
      (node (ref "C4_USB") (pin "2") (pinfunction "2_2") (pintype "passive"))
      (node (ref "C5_USB") (pin "2") (pinfunction "2_2") (pintype "passive"))
      (node (ref "C6_USB") (pin "2") (pinfunction "2_2") (pintype "passive"))
      (node (ref "J1") (pin "1") (pinfunction "1_1") (pintype "passive"))
      (node (ref "J1") (pin "12") (pinfunction "12_12") (pintype "passive"))
      (node (ref "J1") (pin "15") (pinfunction "15_15") (pintype "passive"))
      (node (ref "J1") (pin "2") (pinfunction "2_2") (pintype "passive"))
      (node (ref "J2") (pin "1") (pinfunction "1_1") (pintype "passive"))
      (node (ref "J2") (pin "12") (pinfunction "12_12") (pintype "passive"))
      (node (ref "J2") (pin "13") (pinfunction "13_13") (pintype "passive"))
      (node (ref "J2") (pin "14") (pinfunction "14_14") (pintype "passive"))
      (node (ref "J2") (pin "4") (pinfunction "4_4") (pintype "passive"))
      (node (ref "LED1") (pin "3") (pinfunction "GND_3") (pintype "bidirectional"))
      (node (ref "MODE_BUTTON") (pin "2") (pinfunction "2_2") (pintype "passive"))
      (node (ref "MOLEX") (pin "5") (pinfunction "GND_5") (pintype "power_in"))
      (node (ref "MOLEX") (pin "SH1") (pinfunction "SHIELD_SH1") (pintype "passive"))
      (node (ref "MOLEX") (pin "SH2") (pinfunction "SHIELD_SH2") (pintype "passive"))
      (node (ref "MOLEX") (pin "SH3") (pinfunction "SHIELD_SH3") (pintype "passive"))
      (node (ref "MOLEX") (pin "SH4") (pinfunction "SHIELD_SH4") (pintype "passive"))
      (node (ref "MOLEX") (pin "SH5") (pinfunction "SHIELD_SH5") (pintype "passive"))
      (node (ref "MOLEX") (pin "SH6") (pinfunction "SHIELD_SH6") (pintype "passive"))
      (node (ref "R1_PWRUSB") (pin "1") (pinfunction "1_1") (pintype "passive"))
      (node (ref "R2_BAT") (pin "1") (pinfunction "1_1") (pintype "passive"))
      (node (ref "R2_PWRFB") (pin "1") (pinfunction "1_1") (pintype "passive"))
      (node (ref "R2_PWRUVLO") (pin "1") (pinfunction "1_1") (pintype "passive"))
      (node (ref "R7-ESP1") (pin "1") (pinfunction "1_1") (pintype "passive"))
      (node (ref "RESET_BUTTON") (pin "1") (pinfunction "1_1") (pintype "passive"))
      (node (ref "RESET_BUTTON") (pin "2") (pinfunction "2_2") (pintype "passive"))
      (node (ref "SENSOR2") (pin "1") (pinfunction "GND_1") (pintype "power_in"))
      (node (ref "SENSOR2") (pin "5") (pinfunction "SDO_5") (pintype "bidirectional"))
      (node (ref "SENSOR2") (pin "7") (pinfunction "GND_7") (pintype "power_in"))
      (node (ref "U$1") (pin "GND") (pinfunction "GND1_GND") (pintype "bidirectional"))
      (node (ref "U$1") (pin "GND2") (pinfunction "GND2_GND2") (pintype "bidirectional"))
      (node (ref "U$1") (pin "GND3") (pinfunction "P_GND_GND3") (pintype "bidirectional"))
      (node (ref "U$1") (pin "GND_2") (pinfunction "GND3_GND_2") (pintype "bidirectional"))
      (node (ref "U$3") (pin "P$3") (pinfunction "GND_P$3") (pintype "bidirectional"))
      (node (ref "U2") (pin "11") (pinfunction "PAD_11") (pintype "power_in"))
      (node (ref "U2") (pin "12") (pinfunction "PAD_12") (pintype "power_in"))
      (node (ref "U2") (pin "13") (pinfunction "PAD_13") (pintype "power_in"))
      (node (ref "U2") (pin "14") (pinfunction "PAD_14") (pintype "power_in"))
      (node (ref "U2") (pin "15") (pinfunction "PAD_15") (pintype "power_in"))
      (node (ref "U2") (pin "4") (pinfunction "PGND_4") (pintype "power_in"))
      (node (ref "U2") (pin "9") (pinfunction "GND_9") (pintype "power_in"))
      (node (ref "U3") (pin "2") (pinfunction "VSS_2") (pintype "power_in"))
      (node (ref "U4") (pin "16") (pinfunction "GND_16") (pintype "bidirectional"))
      (node (ref "U4") (pin "6") (pinfunction "GND_6") (pintype "bidirectional"))
    )
    (net (code "51") (name "unconnected-(LED1-INT-Pad5)") (class "Default")
      (node (ref "LED1") (pin "5") (pinfunction "INT_5") (pintype "bidirectional"))
    )
    (net (code "52") (name "unconnected-(LED1-NC-Pad2)") (class "Default")
      (node (ref "LED1") (pin "2") (pinfunction "NC_2") (pintype "no_connect"))
    )
    (net (code "53") (name "unconnected-(MODE_BUTTON-Pad1)") (class "Default")
      (node (ref "MODE_BUTTON") (pin "1") (pinfunction "1_1") (pintype "passive"))
    )
    (net (code "54") (name "unconnected-(MODE_BUTTON-Pad3)") (class "Default")
      (node (ref "MODE_BUTTON") (pin "3") (pinfunction "3_3") (pintype "passive"))
    )
    (net (code "55") (name "unconnected-(MOLEX-ID-Pad4)") (class "Default")
      (node (ref "MOLEX") (pin "4") (pinfunction "ID_4") (pintype "passive"))
    )
    (net (code "56") (name "unconnected-(U$1-NC-PadNC0)") (class "Default")
      (node (ref "U$1") (pin "NC0") (pinfunction "NC_NC0") (pintype "bidirectional"))
    )
    (net (code "57") (name "unconnected-(U$1-PadCLK)") (class "Default")
      (node (ref "U$1") (pin "CLK") (pinfunction "CLK_CLK") (pintype "bidirectional"))
    )
    (net (code "58") (name "unconnected-(U$1-PadCMD)") (class "Default")
      (node (ref "U$1") (pin "CMD") (pinfunction "CMD_CMD") (pintype "bidirectional"))
    )
    (net (code "59") (name "unconnected-(U$1-PadNC1)") (class "Default")
      (node (ref "U$1") (pin "NC1") (pinfunction "NC1_NC1") (pintype "bidirectional"))
    )
    (net (code "60") (name "unconnected-(U$1-PadNC2)") (class "Default")
      (node (ref "U$1") (pin "NC2") (pinfunction "NC2_NC2") (pintype "bidirectional"))
    )
    (net (code "61") (name "unconnected-(U$1-PadSD0)") (class "Default")
      (node (ref "U$1") (pin "SD0") (pinfunction "SD0_SD0") (pintype "bidirectional"))
    )
    (net (code "62") (name "unconnected-(U$1-PadSD1)") (class "Default")
      (node (ref "U$1") (pin "SD1") (pinfunction "SD1_SD1") (pintype "bidirectional"))
    )
    (net (code "63") (name "unconnected-(U$1-PadSD2)") (class "Default")
      (node (ref "U$1") (pin "SD2") (pinfunction "SD2_SD2") (pintype "bidirectional"))
    )
    (net (code "64") (name "unconnected-(U$1-PadSD3)") (class "Default")
      (node (ref "U$1") (pin "SD3") (pinfunction "SD3_SD3") (pintype "bidirectional"))
    )
    (net (code "65") (name "unconnected-(U$1-SENSR_VN-PadSENSOR_VN)") (class "Default")
      (node (ref "U$1") (pin "SENSOR_VN") (pinfunction "SENSR_VN_SENSOR_VN") (pintype "bidirectional"))
    )
    (net (code "66") (name "unconnected-(U$1-SENSR_VP-PadSENSOR_VP)") (class "Default")
      (node (ref "U$1") (pin "SENSOR_VP") (pinfunction "SENSR_VP_SENSOR_VP") (pintype "bidirectional"))
    )
    (net (code "67") (name "unconnected-(U$3-N.C.4-PadP$4)") (class "Default")
      (node (ref "U$3") (pin "P$4") (pinfunction "N.C.4_P$4") (pintype "bidirectional"))
    )
    (net (code "68") (name "unconnected-(U$3-N.C.5-PadP$5)") (class "Default")
      (node (ref "U$3") (pin "P$5") (pinfunction "N.C.5_P$5") (pintype "bidirectional"))
    )
    (net (code "69") (name "unconnected-(U4-CBUS0-Pad18)") (class "Default")
      (node (ref "U4") (pin "18") (pinfunction "CBUS0_18") (pintype "bidirectional"))
    )
    (net (code "70") (name "unconnected-(U4-CBUS3-Pad19)") (class "Default")
      (node (ref "U4") (pin "19") (pinfunction "CBUS3_19") (pintype "bidirectional"))
    )
    (net (code "71") (name "unconnected-(U4-~{CTS}-Pad9)") (class "Default")
      (node (ref "U4") (pin "9") (pinfunction "~{CTS}_9") (pintype "bidirectional"))
    )
    (net (code "72") (name "unconnected-(U4-~{DCD}-Pad8)") (class "Default")
      (node (ref "U4") (pin "8") (pinfunction "~{DCD}_8") (pintype "bidirectional"))
    )
    (net (code "73") (name "unconnected-(U4-~{DSR}-Pad7)") (class "Default")
      (node (ref "U4") (pin "7") (pinfunction "~{DSR}_7") (pintype "bidirectional"))
    )
    (net (code "74") (name "unconnected-(U4-~{RI}-Pad5)") (class "Default")
      (node (ref "U4") (pin "5") (pinfunction "~{RI}_5") (pintype "bidirectional"))
    )
  )
)
